# dw-probe-v2_0.net
KiCad netlist of a schematic drawn in EAGLE
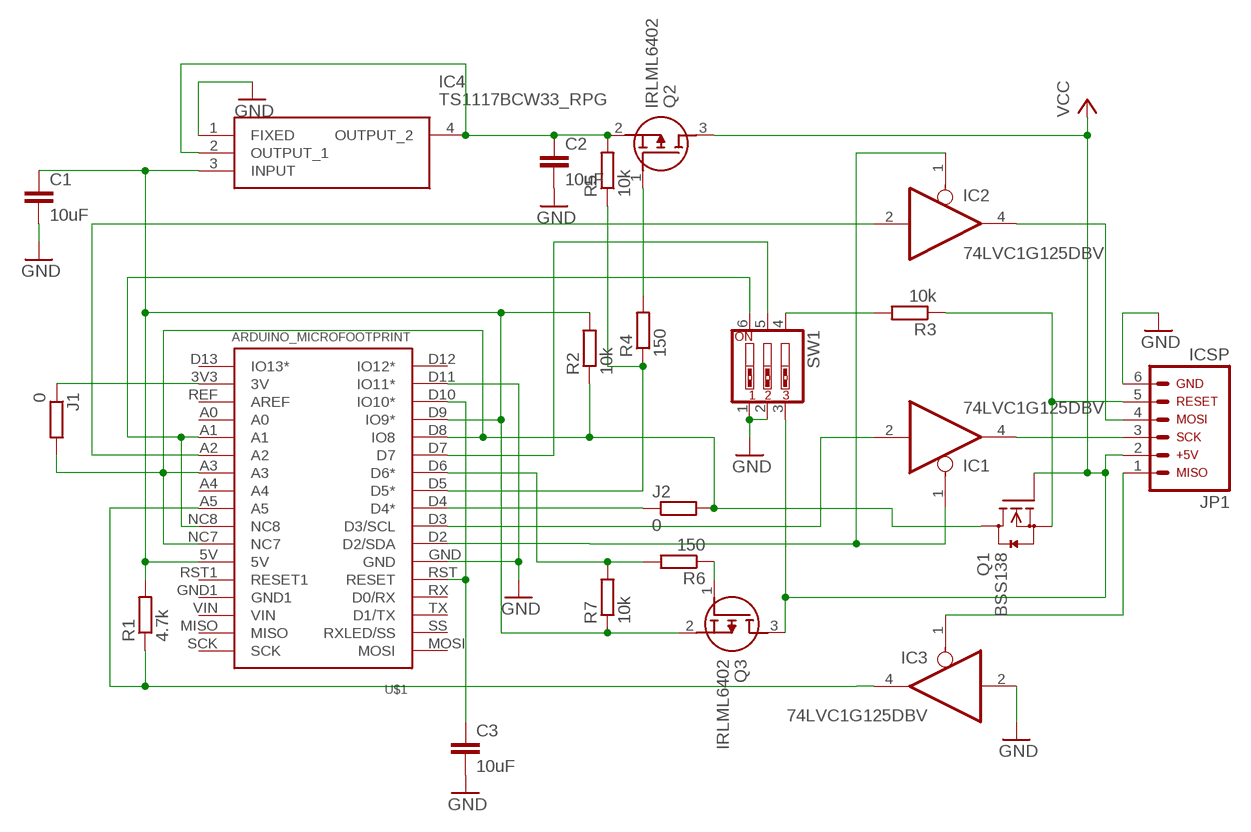
[diagram p0: schematic, sheet 1]

(export (version "E")
  (design (tool "Eeschema 10.0.6"))
  (components
    (comp (ref "C1")
      (value "10uF")
      (footprint "eagle-import:C0805")
      (libsource (lib "eagle-import") (part "C-EUC0805"))
    )
    (comp (ref "C2")
      (value "10uF")
      (footprint "eagle-import:C0805")
      (libsource (lib "eagle-import") (part "C-EUC0805"))
    )
    (comp (ref "C3")
      (value "10uF")
      (footprint "eagle-import:C0805")
      (libsource (lib "eagle-import") (part "C-EUC0805"))
    )
    (comp (ref "IC1")
      (value "74LVC1G125DBV")
      (footprint "eagle-import:SOT23-5")
      (libsource (lib "eagle-import") (part "741G125DBVLVC"))
    )
    (comp (ref "IC2")
      (value "74LVC1G125DBV")
      (footprint "eagle-import:SOT23-5")
      (libsource (lib "eagle-import") (part "741G125DBVLVC"))
    )
    (comp (ref "IC3")
      (value "74LVC1G125DBV")
      (footprint "eagle-import:SOT23-5")
      (libsource (lib "eagle-import") (part "741G125DBVLVC"))
    )
    (comp (ref "IC4")
      (value "TS1117BCW33_RPG")
      (footprint "eagle-import:SOT230P700X190-4N")
      (fields
        (field (name "ARROW_PART_NUMBER") "TS1117BCW33 RPG")
        (field (name "MOUSER_PART_NUMBER") "821-TS1117BCW33RPG")
      )
      (libsource (lib "eagle-import") (part "TS1117BCW33_RPG"))
    )
    (comp (ref "J1")
      (value "0")
      (footprint "eagle-import:R0805")
      (libsource (lib "eagle-import") (part "R-EU_R0805"))
    )
    (comp (ref "J2")
      (value "0")
      (footprint "eagle-import:R0805")
      (libsource (lib "eagle-import") (part "R-EU_R0805"))
    )
    (comp (ref "JP1")
      (value "ARDUINO_CONN-ICSP")
      (footprint "eagle-import:CONN-2X03")
      (libsource (lib "eagle-import") (part "ARDUINO_CONN-ICSP"))
    )
    (comp (ref "Q1")
      (value "BSS138")
      (footprint "eagle-import:SOT23")
      (libsource (lib "eagle-import") (part "BSS138"))
    )
    (comp (ref "Q2")
      (value "IRLML6402")
      (footprint "eagle-import:SOT95P237X112-3N")
      (libsource (lib "eagle-import") (part "IRLML6402"))
    )
    (comp (ref "Q3")
      (value "IRLML6402")
      (footprint "eagle-import:SOT95P237X112-3N")
      (libsource (lib "eagle-import") (part "IRLML6402"))
    )
    (comp (ref "R1")
      (value "4.7k")
      (footprint "eagle-import:R0805")
      (libsource (lib "eagle-import") (part "R-EU_R0805"))
    )
    (comp (ref "R2")
      (value "10k")
      (footprint "eagle-import:R0805")
      (libsource (lib "eagle-import") (part "R-EU_R0805"))
    )
    (comp (ref "R3")
      (value "10k")
      (footprint "eagle-import:R0805")
      (libsource (lib "eagle-import") (part "R-EU_R0805"))
    )
    (comp (ref "R4")
      (value "150")
      (footprint "eagle-import:R0805")
      (libsource (lib "eagle-import") (part "R-EU_R0805"))
    )
    (comp (ref "R5")
      (value "10k")
      (footprint "eagle-import:R0805")
      (libsource (lib "eagle-import") (part "R-EU_R0805"))
    )
    (comp (ref "R6")
      (value "150")
      (footprint "eagle-import:R0805")
      (libsource (lib "eagle-import") (part "R-EU_R0805"))
    )
    (comp (ref "R7")
      (value "10k")
      (footprint "eagle-import:R0805")
      (libsource (lib "eagle-import") (part "R-EU_R0805"))
    )
    (comp (ref "SW1")
      (value "SW_DIP-3")
      (footprint "eagle-import:EDG-03")
      (libsource (lib "eagle-import") (part "SW_DIP-3"))
    )
    (comp (ref "U$1")
      (value "ARDUINO_MICROFOOTPRINT")
      (footprint "eagle-import:ARDUINO-MICRO")
      (libsource (lib "eagle-import") (part "ARDUINO_MICROFOOTPRINT"))
    )
  )
  (nets
    (net (code "1") (name "GND") (class "Default")
      (node (ref "C1") (pin "2") (pinfunction "2_2") (pintype "passive"))
      (node (ref "C2") (pin "2") (pinfunction "2_2") (pintype "passive"))
      (node (ref "C3") (pin "2") (pinfunction "2_2") (pintype "passive"))
      (node (ref "IC3") (pin "2") (pinfunction "I_2") (pintype "input"))
      (node (ref "IC4") (pin "1") (pinfunction "FIXED_1") (pintype "bidirectional"))
      (node (ref "JP1") (pin "6") (pinfunction "6_6") (pintype "passive"))
      (node (ref "SW1") (pin "1") (pinfunction "1_1") (pintype "passive"))
      (node (ref "SW1") (pin "2") (pinfunction "2_2") (pintype "passive"))
      (node (ref "U$1") (pin "D11") (pinfunction "IO11*_D11") (pintype "bidirectional"))
      (node (ref "U$1") (pin "GND") (pinfunction "GND_GND") (pintype "bidirectional"))
    )
    (net (code "2") (name "Net-(IC1A-I)") (class "Default")
      (node (ref "IC1") (pin "2") (pinfunction "I_2") (pintype "input"))
      (node (ref "U$1") (pin "D3") (pinfunction "D3/SCL_D3") (pintype "bidirectional"))
    )
    (net (code "3") (name "Net-(IC1A-O)") (class "Default")
      (node (ref "IC1") (pin "4") (pinfunction "O_4") (pintype "tri_state"))
      (node (ref "JP1") (pin "3") (pinfunction "3_3") (pintype "passive"))
    )
    (net (code "4") (name "Net-(IC1A-OE)") (class "Default")
      (node (ref "IC1") (pin "1") (pinfunction "OE_1") (pintype "input"))
      (node (ref "IC2") (pin "1") (pinfunction "OE_1") (pintype "input"))
      (node (ref "U$1") (pin "D2") (pinfunction "D2/SDA_D2") (pintype "bidirectional"))
    )
    (net (code "5") (name "Net-(IC2A-I)") (class "Default")
      (node (ref "IC2") (pin "2") (pinfunction "I_2") (pintype "input"))
      (node (ref "U$1") (pin "A2") (pinfunction "A2_A2") (pintype "bidirectional"))
    )
    (net (code "6") (name "Net-(IC2A-O)") (class "Default")
      (node (ref "IC2") (pin "4") (pinfunction "O_4") (pintype "tri_state"))
      (node (ref "JP1") (pin "4") (pinfunction "4_4") (pintype "passive"))
    )
    (net (code "7") (name "Net-(IC3A-O)") (class "Default")
      (node (ref "IC3") (pin "4") (pinfunction "O_4") (pintype "tri_state"))
      (node (ref "R1") (pin "1") (pinfunction "1_1") (pintype "passive"))
      (node (ref "U$1") (pin "A5") (pinfunction "A5_A5") (pintype "bidirectional"))
    )
    (net (code "8") (name "Net-(IC3A-OE)") (class "Default")
      (node (ref "IC3") (pin "1") (pinfunction "OE_1") (pintype "input"))
      (node (ref "JP1") (pin "1") (pinfunction "1_1") (pintype "passive"))
    )
    (net (code "9") (name "Net-(IC4-INPUT)") (class "Default")
      (node (ref "C1") (pin "1") (pinfunction "1_1") (pintype "passive"))
      (node (ref "IC4") (pin "3") (pinfunction "INPUT_3") (pintype "bidirectional"))
      (node (ref "Q3") (pin "2") (pinfunction "S_2") (pintype "bidirectional"))
      (node (ref "R1") (pin "2") (pinfunction "2_2") (pintype "passive"))
      (node (ref "R2") (pin "2") (pinfunction "2_2") (pintype "passive"))
      (node (ref "R7") (pin "1") (pinfunction "1_1") (pintype "passive"))
      (node (ref "U$1") (pin "5V") (pinfunction "5V_5V") (pintype "bidirectional"))
      (node (ref "U$1") (pin "D9") (pinfunction "IO9*_D9") (pintype "bidirectional"))
    )
    (net (code "10") (name "Net-(IC4-OUTPUT_1)") (class "Default")
      (node (ref "C2") (pin "1") (pinfunction "1_1") (pintype "passive"))
      (node (ref "IC4") (pin "2") (pinfunction "OUTPUT_1_2") (pintype "bidirectional"))
      (node (ref "IC4") (pin "4") (pinfunction "OUTPUT_2_4") (pintype "bidirectional"))
      (node (ref "Q2") (pin "2") (pinfunction "S_2") (pintype "bidirectional"))
      (node (ref "R5") (pin "2") (pinfunction "2_2") (pintype "passive"))
    )
    (net (code "11") (name "Net-(Q1-D)") (class "Default")
      (node (ref "J1") (pin "2") (pinfunction "2_2") (pintype "passive"))
      (node (ref "J2") (pin "2") (pinfunction "2_2") (pintype "passive"))
      (node (ref "Q1") (pin "3") (pinfunction "D_3") (pintype "passive"))
      (node (ref "R2") (pin "1") (pinfunction "1_1") (pintype "passive"))
      (node (ref "U$1") (pin "A3") (pinfunction "A3_A3") (pintype "bidirectional"))
      (node (ref "U$1") (pin "D8") (pinfunction "IO8_D8") (pintype "bidirectional"))
      (node (ref "U$1") (pin "NC7") (pinfunction "NC7_NC7") (pintype "bidirectional"))
    )
    (net (code "12") (name "Net-(Q1-S)") (class "Default")
      (node (ref "JP1") (pin "5") (pinfunction "5_5") (pintype "passive"))
      (node (ref "Q1") (pin "2") (pinfunction "S_2") (pintype "passive"))
      (node (ref "R3") (pin "1") (pinfunction "1_1") (pintype "passive"))
    )
    (net (code "13") (name "Net-(Q2-G)") (class "Default")
      (node (ref "Q2") (pin "1") (pinfunction "G_1") (pintype "bidirectional"))
      (node (ref "R4") (pin "2") (pinfunction "2_2") (pintype "passive"))
    )
    (net (code "14") (name "Net-(Q3-G)") (class "Default")
      (node (ref "Q3") (pin "1") (pinfunction "G_1") (pintype "bidirectional"))
      (node (ref "R6") (pin "1") (pinfunction "1_1") (pintype "passive"))
    )
    (net (code "15") (name "Net-(R3-Pad2)") (class "Default")
      (node (ref "R3") (pin "2") (pinfunction "2_2") (pintype "passive"))
      (node (ref "SW1") (pin "4") (pinfunction "4_4") (pintype "passive"))
    )
    (net (code "16") (name "Net-(SW1-Pad5)") (class "Default")
      (node (ref "SW1") (pin "5") (pinfunction "5_5") (pintype "passive"))
      (node (ref "U$1") (pin "D7") (pinfunction "D7_D7") (pintype "bidirectional"))
    )
    (net (code "17") (name "Net-(SW1-Pad6)") (class "Default")
      (node (ref "SW1") (pin "6") (pinfunction "6_6") (pintype "passive"))
      (node (ref "U$1") (pin "A1") (pinfunction "A1_A1") (pintype "bidirectional"))
      (node (ref "U$1") (pin "NC8") (pinfunction "NC8_NC8") (pintype "bidirectional"))
    )
    (net (code "18") (name "Net-(U$1-3V)") (class "Default")
      (node (ref "J1") (pin "1") (pinfunction "1_1") (pintype "passive"))
      (node (ref "U$1") (pin "3V3") (pinfunction "3V_3V3") (pintype "bidirectional"))
    )
    (net (code "19") (name "Net-(U$1-D4*)") (class "Default")
      (node (ref "J2") (pin "1") (pinfunction "1_1") (pintype "passive"))
      (node (ref "U$1") (pin "D4") (pinfunction "D4*_D4") (pintype "bidirectional"))
    )
    (net (code "20") (name "Net-(U$1-D5*)") (class "Default")
      (node (ref "R4") (pin "1") (pinfunction "1_1") (pintype "passive"))
      (node (ref "R5") (pin "1") (pinfunction "1_1") (pintype "passive"))
      (node (ref "U$1") (pin "D5") (pinfunction "D5*_D5") (pintype "bidirectional"))
    )
    (net (code "21") (name "Net-(U$1-D6*)") (class "Default")
      (node (ref "R6") (pin "2") (pinfunction "2_2") (pintype "passive"))
      (node (ref "R7") (pin "2") (pinfunction "2_2") (pintype "passive"))
      (node (ref "U$1") (pin "D6") (pinfunction "D6*_D6") (pintype "bidirectional"))
    )
    (net (code "22") (name "Net-(U$1-IO10*)") (class "Default")
      (node (ref "C3") (pin "1") (pinfunction "1_1") (pintype "passive"))
      (node (ref "U$1") (pin "D10") (pinfunction "IO10*_D10") (pintype "bidirectional"))
      (node (ref "U$1") (pin "RST") (pinfunction "RESET_RST") (pintype "bidirectional"))
    )
    (net (code "23") (name "VCC") (class "Default")
      (node (ref "JP1") (pin "2") (pinfunction "2_2") (pintype "passive"))
      (node (ref "Q1") (pin "1") (pinfunction "G_1") (pintype "passive"))
      (node (ref "Q2") (pin "3") (pinfunction "D_3") (pintype "bidirectional"))
      (node (ref "Q3") (pin "3") (pinfunction "D_3") (pintype "bidirectional"))
      (node (ref "SW1") (pin "3") (pinfunction "3_3") (pintype "passive"))
    )
    (net (code "24") (name "unconnected-(U$1-AREF-PadREF)") (class "Default")
      (node (ref "U$1") (pin "REF") (pinfunction "AREF_REF") (pintype "bidirectional"))
    )
    (net (code "25") (name "unconnected-(U$1-D0{slash}RX-PadRX)") (class "Default")
      (node (ref "U$1") (pin "RX") (pinfunction "D0/RX_RX") (pintype "bidirectional"))
    )
    (net (code "26") (name "unconnected-(U$1-D1{slash}TX-PadTX)") (class "Default")
      (node (ref "U$1") (pin "TX") (pinfunction "D1/TX_TX") (pintype "bidirectional"))
    )
    (net (code "27") (name "unconnected-(U$1-IO12*-PadD12)") (class "Default")
      (node (ref "U$1") (pin "D12") (pinfunction "IO12*_D12") (pintype "bidirectional"))
    )
    (net (code "28") (name "unconnected-(U$1-IO13*-PadD13)") (class "Default")
      (node (ref "U$1") (pin "D13") (pinfunction "IO13*_D13") (pintype "bidirectional"))
    )
    (net (code "29") (name "unconnected-(U$1-PadA0)") (class "Default")
      (node (ref "U$1") (pin "A0") (pinfunction "A0_A0") (pintype "bidirectional"))
    )
    (net (code "30") (name "unconnected-(U$1-PadA4)") (class "Default")
      (node (ref "U$1") (pin "A4") (pinfunction "A4_A4") (pintype "bidirectional"))
    )
    (net (code "31") (name "unconnected-(U$1-PadGND1)") (class "Default")
      (node (ref "U$1") (pin "GND1") (pinfunction "GND1_GND1") (pintype "bidirectional"))
    )
    (net (code "32") (name "unconnected-(U$1-PadMISO)") (class "Default")
      (node (ref "U$1") (pin "MISO") (pinfunction "MISO_MISO") (pintype "bidirectional"))
    )
    (net (code "33") (name "unconnected-(U$1-PadMOSI)") (class "Default")
      (node (ref "U$1") (pin "MOSI") (pinfunction "MOSI_MOSI") (pintype "bidirectional"))
    )
    (net (code "34") (name "unconnected-(U$1-PadSCK)") (class "Default")
      (node (ref "U$1") (pin "SCK") (pinfunction "SCK_SCK") (pintype "bidirectional"))
    )
    (net (code "35") (name "unconnected-(U$1-PadVIN)") (class "Default")
      (node (ref "U$1") (pin "VIN") (pinfunction "VIN_VIN") (pintype "bidirectional"))
    )
    (net (code "36") (name "unconnected-(U$1-RESET1-PadRST1)") (class "Default")
      (node (ref "U$1") (pin "RST1") (pinfunction "RESET1_RST1") (pintype "bidirectional"))
    )
    (net (code "37") (name "unconnected-(U$1-RXLED{slash}SS-PadSS)") (class "Default")
      (node (ref "U$1") (pin "SS") (pinfunction "RXLED/SS_SS") (pintype "bidirectional"))
    )
  )
)
